# ArduinoAirQuailtyTop.net
KiCad netlist of a schematic drawn in EAGLE
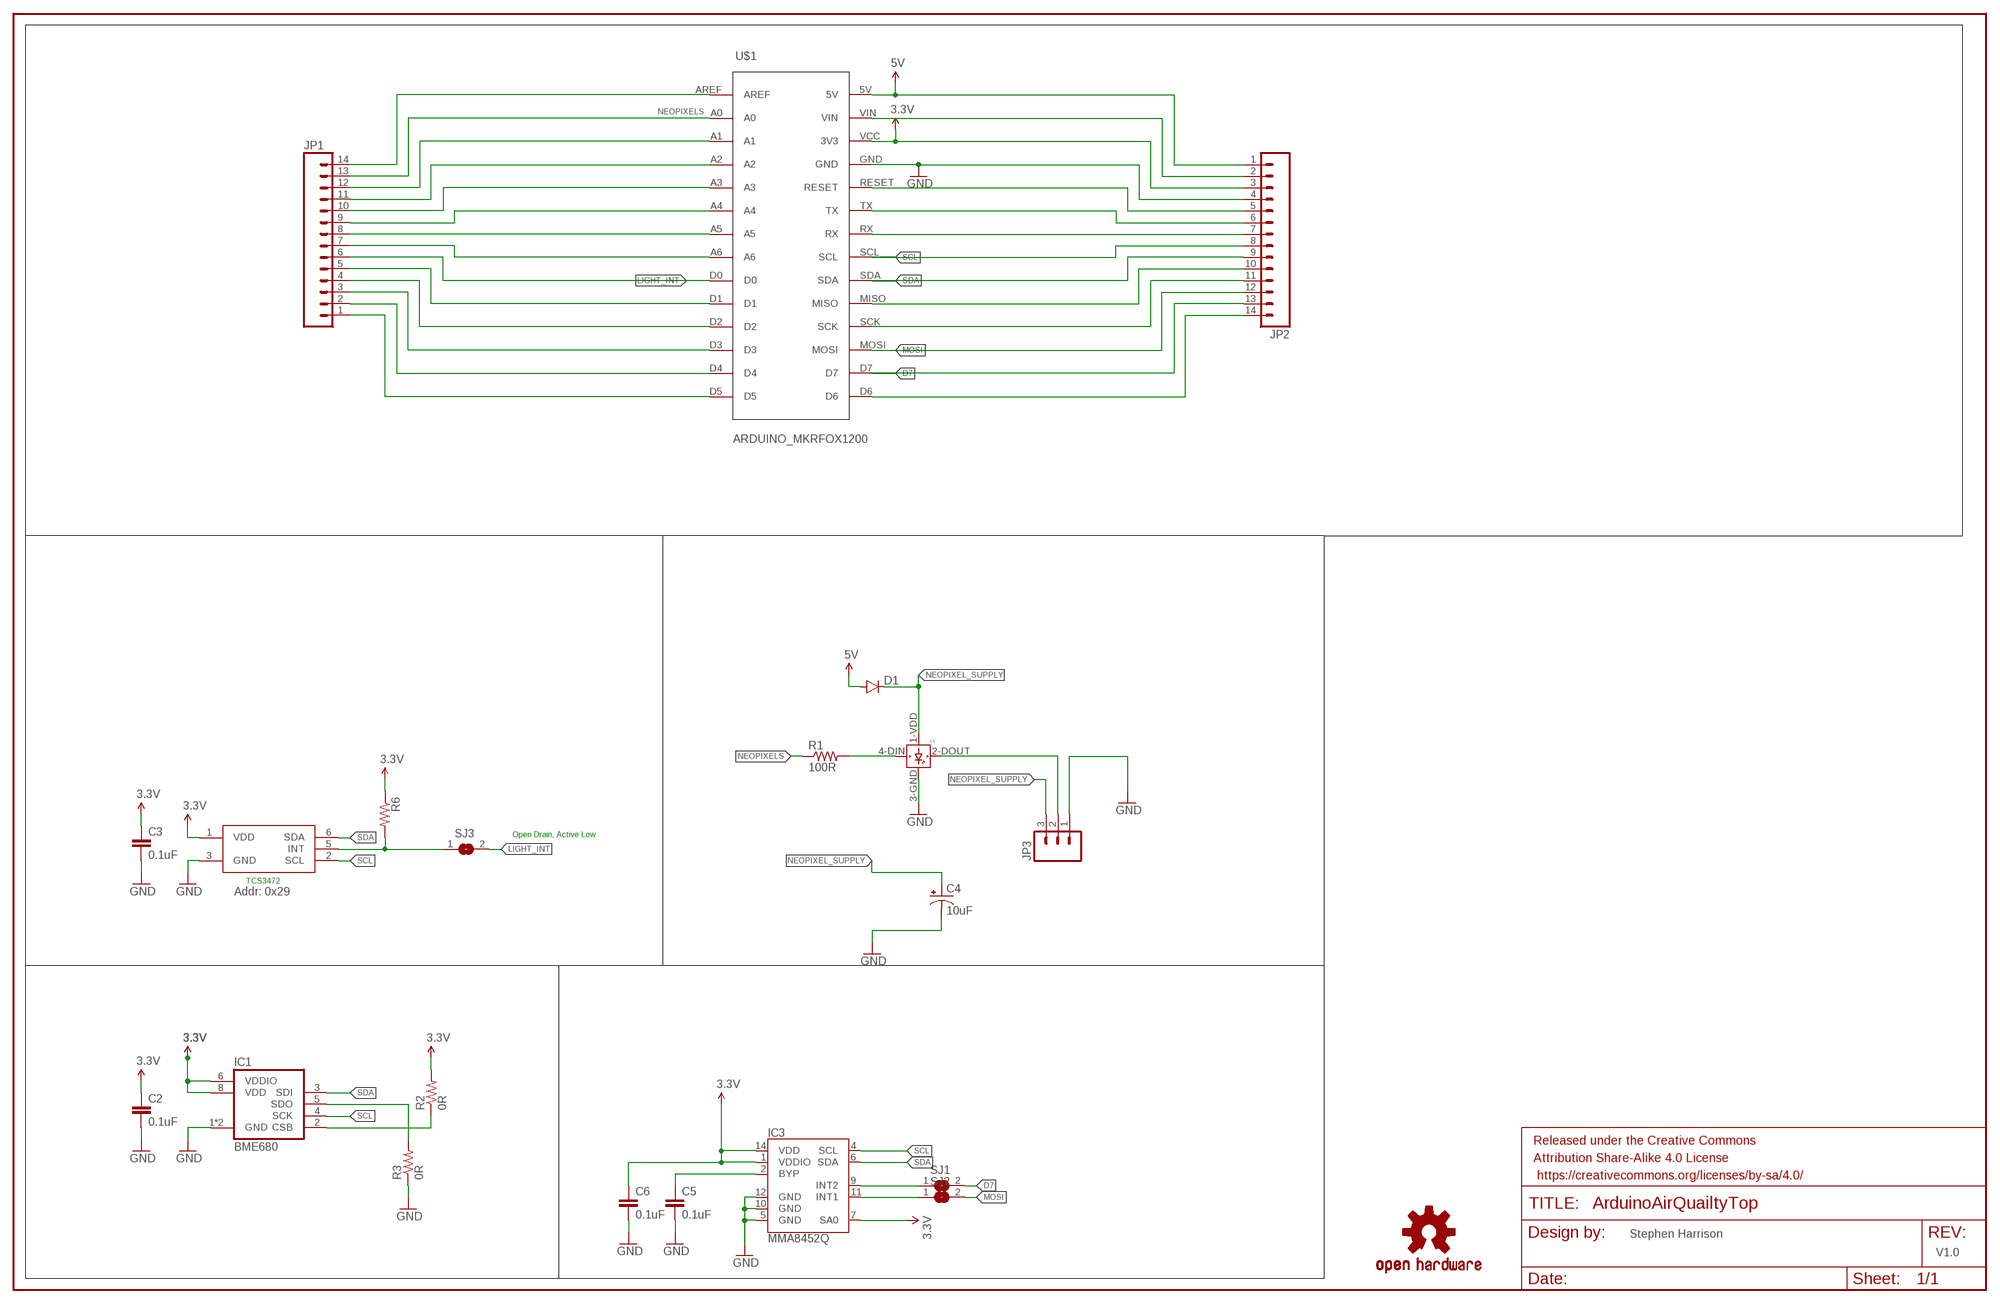
[diagram p0: schematic, sheet 1]

(export (version "E")
  (design (tool "Eeschema 10.0.6"))
  (components
    (comp (ref "C2")
      (value "0.1uF")
      (footprint "eagle-import:0805")
      (libsource (lib "eagle-import") (part "CAP0805"))
    )
    (comp (ref "C3")
      (value "0.1uF")
      (footprint "eagle-import:0805")
      (libsource (lib "eagle-import") (part "CAP0805"))
    )
    (comp (ref "C4")
      (value "10uF")
      (footprint "eagle-import:EIA3216")
      (libsource (lib "eagle-import") (part "10UF-16V-10%(TANT)"))
    )
    (comp (ref "C5")
      (value "0.1uF")
      (footprint "eagle-import:0805")
      (libsource (lib "eagle-import") (part "CAP0805"))
    )
    (comp (ref "C6")
      (value "0.1uF")
      (footprint "eagle-import:0805")
      (libsource (lib "eagle-import") (part "CAP0805"))
    )
    (comp (ref "D1")
      (value "DIODESMA")
      (footprint "eagle-import:SMA-DIODE")
      (libsource (lib "eagle-import") (part "DIODESMA"))
    )
    (comp (ref "FRAME1")
      (value "FRAME-LEDGER")
      (footprint "eagle-import:CREATIVE_COMMONS")
      (libsource (lib "eagle-import") (part "FRAME-LEDGER"))
    )
    (comp (ref "IC1")
      (value "BME680")
      (footprint "eagle-import:BME680")
      (libsource (lib "eagle-import") (part "BME680"))
    )
    (comp (ref "IC2")
      (value "TCS34725FN")
      (footprint "eagle-import:FN-6")
      (libsource (lib "eagle-import") (part "TCS3472"))
    )
    (comp (ref "IC3")
      (value "MMA8452Q")
      (footprint "eagle-import:QFN-16_0.5MM")
      (libsource (lib "eagle-import") (part "MMA8452Q"))
    )
    (comp (ref "JP1")
      (value "M14")
      (footprint "eagle-import:1X14")
      (libsource (lib "eagle-import") (part "M14"))
    )
    (comp (ref "JP2")
      (value "M14")
      (footprint "eagle-import:1X14")
      (libsource (lib "eagle-import") (part "M14"))
    )
    (comp (ref "JP3")
      (value "M03POLAR")
      (footprint "eagle-import:MOLEX-1X3")
      (libsource (lib "eagle-import") (part "M03POLAR"))
    )
    (comp (ref "L1")
      (value "WS2812B")
      (footprint "eagle-import:WS2812B")
      (libsource (lib "eagle-import") (part "WS2812B"))
    )
    (comp (ref "LOGO1")
      (value "OSHW-LOGOM")
      (footprint "eagle-import:OSHW-LOGO-M")
      (libsource (lib "eagle-import") (part "OSHW-LOGOM"))
    )
    (comp (ref "R1")
      (value "100R")
      (footprint "eagle-import:0805")
      (libsource (lib "eagle-import") (part "RESISTOR0805-RES"))
    )
    (comp (ref "R2")
      (value "0R")
      (footprint "eagle-import:0805")
      (libsource (lib "eagle-import") (part "RESISTOR0805-RES"))
    )
    (comp (ref "R3")
      (value "0R")
      (footprint "eagle-import:0805")
      (libsource (lib "eagle-import") (part "RESISTOR0805-RES"))
    )
    (comp (ref "R6")
      (value "RESISTOR0805-RES")
      (footprint "eagle-import:0805")
      (libsource (lib "eagle-import") (part "RESISTOR0805-RES"))
    )
    (comp (ref "SJ1") (value "SJ") (footprint "eagle-import:SJ") (libsource (lib "eagle-import") (part "SJ")))
    (comp (ref "SJ2") (value "SJ") (footprint "eagle-import:SJ") (libsource (lib "eagle-import") (part "SJ")))
    (comp (ref "SJ3") (value "SJ") (footprint "eagle-import:SJ") (libsource (lib "eagle-import") (part "SJ")))
    (comp (ref "U$1")
      (value "ARDUINO_MKRFOX1200")
      (footprint "eagle-import:ARDUINO_MKRFOX1200")
      (libsource (lib "eagle-import") (part "ARDUINO_MKRFOX1200"))
    )
  )
  (nets
    (net (code "1") (name "3.3V") (class "Default")
      (node (ref "C2") (pin "1") (pinfunction "1_1") (pintype "passive"))
      (node (ref "C3") (pin "1") (pinfunction "1_1") (pintype "passive"))
      (node (ref "C6") (pin "1") (pinfunction "1_1") (pintype "passive"))
      (node (ref "IC1") (pin "6") (pinfunction "VDDIO_6") (pintype "power_in"))
      (node (ref "IC1") (pin "8") (pinfunction "VDD_8") (pintype "power_in"))
      (node (ref "IC2") (pin "1") (pinfunction "VDD_1") (pintype "bidirectional"))
      (node (ref "IC3") (pin "1") (pinfunction "VDDIO_1") (pintype "bidirectional"))
      (node (ref "IC3") (pin "14") (pinfunction "VDD_14") (pintype "bidirectional"))
      (node (ref "IC3") (pin "7") (pinfunction "SA0_7") (pintype "bidirectional"))
      (node (ref "JP2") (pin "3") (pinfunction "3_3") (pintype "passive"))
      (node (ref "R2") (pin "2") (pinfunction "2_2") (pintype "passive"))
      (node (ref "R6") (pin "1") (pinfunction "1_1") (pintype "passive"))
      (node (ref "U$1") (pin "VCC") (pinfunction "3V3_VCC") (pintype "output"))
    )
    (net (code "2") (name "5V") (class "Default")
      (node (ref "D1") (pin "A") (pinfunction "A_A") (pintype "passive"))
      (node (ref "JP2") (pin "1") (pinfunction "1_1") (pintype "passive"))
      (node (ref "U$1") (pin "5V") (pinfunction "5V_5V") (pintype "output"))
    )
    (net (code "3") (name "D7") (class "Default")
      (node (ref "JP2") (pin "13") (pinfunction "13_13") (pintype "passive"))
      (node (ref "SJ1") (pin "2") (pinfunction "2_2") (pintype "passive"))
      (node (ref "U$1") (pin "D7") (pinfunction "D7_D7") (pintype "bidirectional"))
    )
    (net (code "4") (name "GND") (class "Default")
      (node (ref "C2") (pin "2") (pinfunction "2_2") (pintype "passive"))
      (node (ref "C3") (pin "2") (pinfunction "2_2") (pintype "passive"))
      (node (ref "C4") (pin "C") (pinfunction "-_C") (pintype "passive"))
      (node (ref "C5") (pin "2") (pinfunction "2_2") (pintype "passive"))
      (node (ref "C6") (pin "2") (pinfunction "2_2") (pintype "passive"))
      (node (ref "IC1") (pin "1") (pinfunction "GND_1") (pintype "power_in"))
      (node (ref "IC1") (pin "7") (pinfunction "GND_7") (pintype "power_in"))
      (node (ref "IC2") (pin "3") (pinfunction "GND_3") (pintype "bidirectional"))
      (node (ref "IC3") (pin "10") (pinfunction "GND_10") (pintype "bidirectional"))
      (node (ref "IC3") (pin "12") (pinfunction "GND_12") (pintype "bidirectional"))
      (node (ref "IC3") (pin "5") (pinfunction "GND_5") (pintype "bidirectional"))
      (node (ref "JP2") (pin "4") (pinfunction "4_4") (pintype "passive"))
      (node (ref "JP3") (pin "1") (pinfunction "1_1") (pintype "passive"))
      (node (ref "L1") (pin "3-GND") (pinfunction "GND_3-GND") (pintype "bidirectional"))
      (node (ref "R3") (pin "1") (pinfunction "1_1") (pintype "passive"))
      (node (ref "U$1") (pin "GND") (pinfunction "GND_GND") (pintype "power_in"))
    )
    (net (code "5") (name "LIGHT_INT") (class "Default")
      (node (ref "JP1") (pin "6") (pinfunction "6_6") (pintype "passive"))
      (node (ref "SJ3") (pin "2") (pinfunction "2_2") (pintype "passive"))
      (node (ref "U$1") (pin "D0") (pinfunction "D0_D0") (pintype "bidirectional"))
    )
    (net (code "6") (name "MOSI") (class "Default")
      (node (ref "JP2") (pin "12") (pinfunction "12_12") (pintype "passive"))
      (node (ref "SJ2") (pin "2") (pinfunction "2_2") (pintype "passive"))
      (node (ref "U$1") (pin "MOSI") (pinfunction "MOSI_MOSI") (pintype "bidirectional"))
    )
    (net (code "7") (name "NEOPIXELS") (class "Default")
      (node (ref "JP1") (pin "13") (pinfunction "13_13") (pintype "passive"))
      (node (ref "R1") (pin "1") (pinfunction "1_1") (pintype "passive"))
      (node (ref "U$1") (pin "A0") (pinfunction "A0_A0") (pintype "bidirectional"))
    )
    (net (code "8") (name "NEOPIXEL_SUPPLY") (class "Default")
      (node (ref "C4") (pin "A") (pinfunction "+_A") (pintype "passive"))
      (node (ref "D1") (pin "C") (pinfunction "C_C") (pintype "passive"))
      (node (ref "JP3") (pin "3") (pinfunction "3_3") (pintype "passive"))
      (node (ref "L1") (pin "1-VDD") (pinfunction "VDD_1-VDD") (pintype "bidirectional"))
    )
    (net (code "9") (name "Net-(IC1-CSB)") (class "Default")
      (node (ref "IC1") (pin "2") (pinfunction "CSB_2") (pintype "input"))
      (node (ref "R2") (pin "1") (pinfunction "1_1") (pintype "passive"))
    )
    (net (code "10") (name "Net-(IC1-SDO)") (class "Default")
      (node (ref "IC1") (pin "5") (pinfunction "SDO_5") (pintype "output"))
      (node (ref "R3") (pin "2") (pinfunction "2_2") (pintype "passive"))
    )
    (net (code "11") (name "Net-(IC2-INT)") (class "Default")
      (node (ref "IC2") (pin "5") (pinfunction "INT_5") (pintype "bidirectional"))
      (node (ref "R6") (pin "2") (pinfunction "2_2") (pintype "passive"))
      (node (ref "SJ3") (pin "1") (pinfunction "1_1") (pintype "passive"))
    )
    (net (code "12") (name "Net-(IC3-BYP)") (class "Default")
      (node (ref "C5") (pin "1") (pinfunction "1_1") (pintype "passive"))
      (node (ref "IC3") (pin "2") (pinfunction "BYP_2") (pintype "bidirectional"))
    )
    (net (code "13") (name "Net-(IC3-INT1)") (class "Default")
      (node (ref "IC3") (pin "11") (pinfunction "INT1_11") (pintype "bidirectional"))
      (node (ref "SJ2") (pin "1") (pinfunction "1_1") (pintype "passive"))
    )
    (net (code "14") (name "Net-(IC3-INT2)") (class "Default")
      (node (ref "IC3") (pin "9") (pinfunction "INT2_9") (pintype "bidirectional"))
      (node (ref "SJ1") (pin "1") (pinfunction "1_1") (pintype "passive"))
    )
    (net (code "15") (name "Net-(JP1-Pad1)") (class "Default")
      (node (ref "JP1") (pin "1") (pinfunction "1_1") (pintype "passive"))
      (node (ref "U$1") (pin "D5") (pinfunction "D5_D5") (pintype "bidirectional"))
    )
    (net (code "16") (name "Net-(JP1-Pad2)") (class "Default")
      (node (ref "JP1") (pin "2") (pinfunction "2_2") (pintype "passive"))
      (node (ref "U$1") (pin "D4") (pinfunction "D4_D4") (pintype "bidirectional"))
    )
    (net (code "17") (name "Net-(JP1-Pad3)") (class "Default")
      (node (ref "JP1") (pin "3") (pinfunction "3_3") (pintype "passive"))
      (node (ref "U$1") (pin "D3") (pinfunction "D3_D3") (pintype "bidirectional"))
    )
    (net (code "18") (name "Net-(JP1-Pad4)") (class "Default")
      (node (ref "JP1") (pin "4") (pinfunction "4_4") (pintype "passive"))
      (node (ref "U$1") (pin "D2") (pinfunction "D2_D2") (pintype "bidirectional"))
    )
    (net (code "19") (name "Net-(JP1-Pad5)") (class "Default")
      (node (ref "JP1") (pin "5") (pinfunction "5_5") (pintype "passive"))
      (node (ref "U$1") (pin "D1") (pinfunction "D1_D1") (pintype "bidirectional"))
    )
    (net (code "20") (name "Net-(JP1-Pad7)") (class "Default")
      (node (ref "JP1") (pin "7") (pinfunction "7_7") (pintype "passive"))
      (node (ref "U$1") (pin "A6") (pinfunction "A6_A6") (pintype "bidirectional"))
    )
    (net (code "21") (name "Net-(JP1-Pad8)") (class "Default")
      (node (ref "JP1") (pin "8") (pinfunction "8_8") (pintype "passive"))
      (node (ref "U$1") (pin "A5") (pinfunction "A5_A5") (pintype "bidirectional"))
    )
    (net (code "22") (name "Net-(JP1-Pad9)") (class "Default")
      (node (ref "JP1") (pin "9") (pinfunction "9_9") (pintype "passive"))
      (node (ref "U$1") (pin "A4") (pinfunction "A4_A4") (pintype "bidirectional"))
    )
    (net (code "23") (name "Net-(JP1-Pad10)") (class "Default")
      (node (ref "JP1") (pin "10") (pinfunction "10_10") (pintype "passive"))
      (node (ref "U$1") (pin "A3") (pinfunction "A3_A3") (pintype "bidirectional"))
    )
    (net (code "24") (name "Net-(JP1-Pad11)") (class "Default")
      (node (ref "JP1") (pin "11") (pinfunction "11_11") (pintype "passive"))
      (node (ref "U$1") (pin "A2") (pinfunction "A2_A2") (pintype "bidirectional"))
    )
    (net (code "25") (name "Net-(JP1-Pad12)") (class "Default")
      (node (ref "JP1") (pin "12") (pinfunction "12_12") (pintype "passive"))
      (node (ref "U$1") (pin "A1") (pinfunction "A1_A1") (pintype "bidirectional"))
    )
    (net (code "26") (name "Net-(JP1-Pad14)") (class "Default")
      (node (ref "JP1") (pin "14") (pinfunction "14_14") (pintype "passive"))
      (node (ref "U$1") (pin "AREF") (pinfunction "AREF_AREF") (pintype "bidirectional"))
    )
    (net (code "27") (name "Net-(JP2-Pad2)") (class "Default")
      (node (ref "JP2") (pin "2") (pinfunction "2_2") (pintype "passive"))
      (node (ref "U$1") (pin "VIN") (pinfunction "VIN_VIN") (pintype "input"))
    )
    (net (code "28") (name "Net-(JP2-Pad5)") (class "Default")
      (node (ref "JP2") (pin "5") (pinfunction "5_5") (pintype "passive"))
      (node (ref "U$1") (pin "RESET") (pinfunction "RESET_RESET") (pintype "bidirectional"))
    )
    (net (code "29") (name "Net-(JP2-Pad6)") (class "Default")
      (node (ref "JP2") (pin "6") (pinfunction "6_6") (pintype "passive"))
      (node (ref "U$1") (pin "TX") (pinfunction "TX_TX") (pintype "bidirectional"))
    )
    (net (code "30") (name "Net-(JP2-Pad7)") (class "Default")
      (node (ref "JP2") (pin "7") (pinfunction "7_7") (pintype "passive"))
      (node (ref "U$1") (pin "RX") (pinfunction "RX_RX") (pintype "bidirectional"))
    )
    (net (code "31") (name "Net-(JP2-Pad10)") (class "Default")
      (node (ref "JP2") (pin "10") (pinfunction "10_10") (pintype "passive"))
      (node (ref "U$1") (pin "MISO") (pinfunction "MISO_MISO") (pintype "bidirectional"))
    )
    (net (code "32") (name "Net-(JP2-Pad11)") (class "Default")
      (node (ref "JP2") (pin "11") (pinfunction "11_11") (pintype "passive"))
      (node (ref "U$1") (pin "SCK") (pinfunction "SCK_SCK") (pintype "bidirectional"))
    )
    (net (code "33") (name "Net-(JP2-Pad14)") (class "Default")
      (node (ref "JP2") (pin "14") (pinfunction "14_14") (pintype "passive"))
      (node (ref "U$1") (pin "D6") (pinfunction "D6_D6") (pintype "bidirectional"))
    )
    (net (code "34") (name "Net-(L1-DIN)") (class "Default")
      (node (ref "L1") (pin "4-DIN") (pinfunction "DIN_4-DIN") (pintype "input"))
      (node (ref "R1") (pin "2") (pinfunction "2_2") (pintype "passive"))
    )
    (net (code "35") (name "Net-(L1-DOUT)") (class "Default")
      (node (ref "JP3") (pin "2") (pinfunction "2_2") (pintype "passive"))
      (node (ref "L1") (pin "2-DOUT") (pinfunction "DOUT_2-DOUT") (pintype "output"))
    )
    (net (code "36") (name "SCL") (class "Default")
      (node (ref "IC1") (pin "4") (pinfunction "SCK_4") (pintype "input"))
      (node (ref "IC2") (pin "2") (pinfunction "SCL_2") (pintype "bidirectional"))
      (node (ref "IC3") (pin "4") (pinfunction "SCL_4") (pintype "bidirectional"))
      (node (ref "JP2") (pin "8") (pinfunction "8_8") (pintype "passive"))
      (node (ref "U$1") (pin "SCL") (pinfunction "SCL_SCL") (pintype "bidirectional"))
    )
    (net (code "37") (name "SDA") (class "Default")
      (node (ref "IC1") (pin "3") (pinfunction "SDI_3") (pintype "input"))
      (node (ref "IC2") (pin "6") (pinfunction "SDA_6") (pintype "bidirectional"))
      (node (ref "IC3") (pin "6") (pinfunction "SDA_6") (pintype "bidirectional"))
      (node (ref "JP2") (pin "9") (pinfunction "9_9") (pintype "passive"))
      (node (ref "U$1") (pin "SDA") (pinfunction "SDA_SDA") (pintype "bidirectional"))
    )
  )
)
